# blinds_new.net
KiCad netlist of a schematic drawn in EAGLE
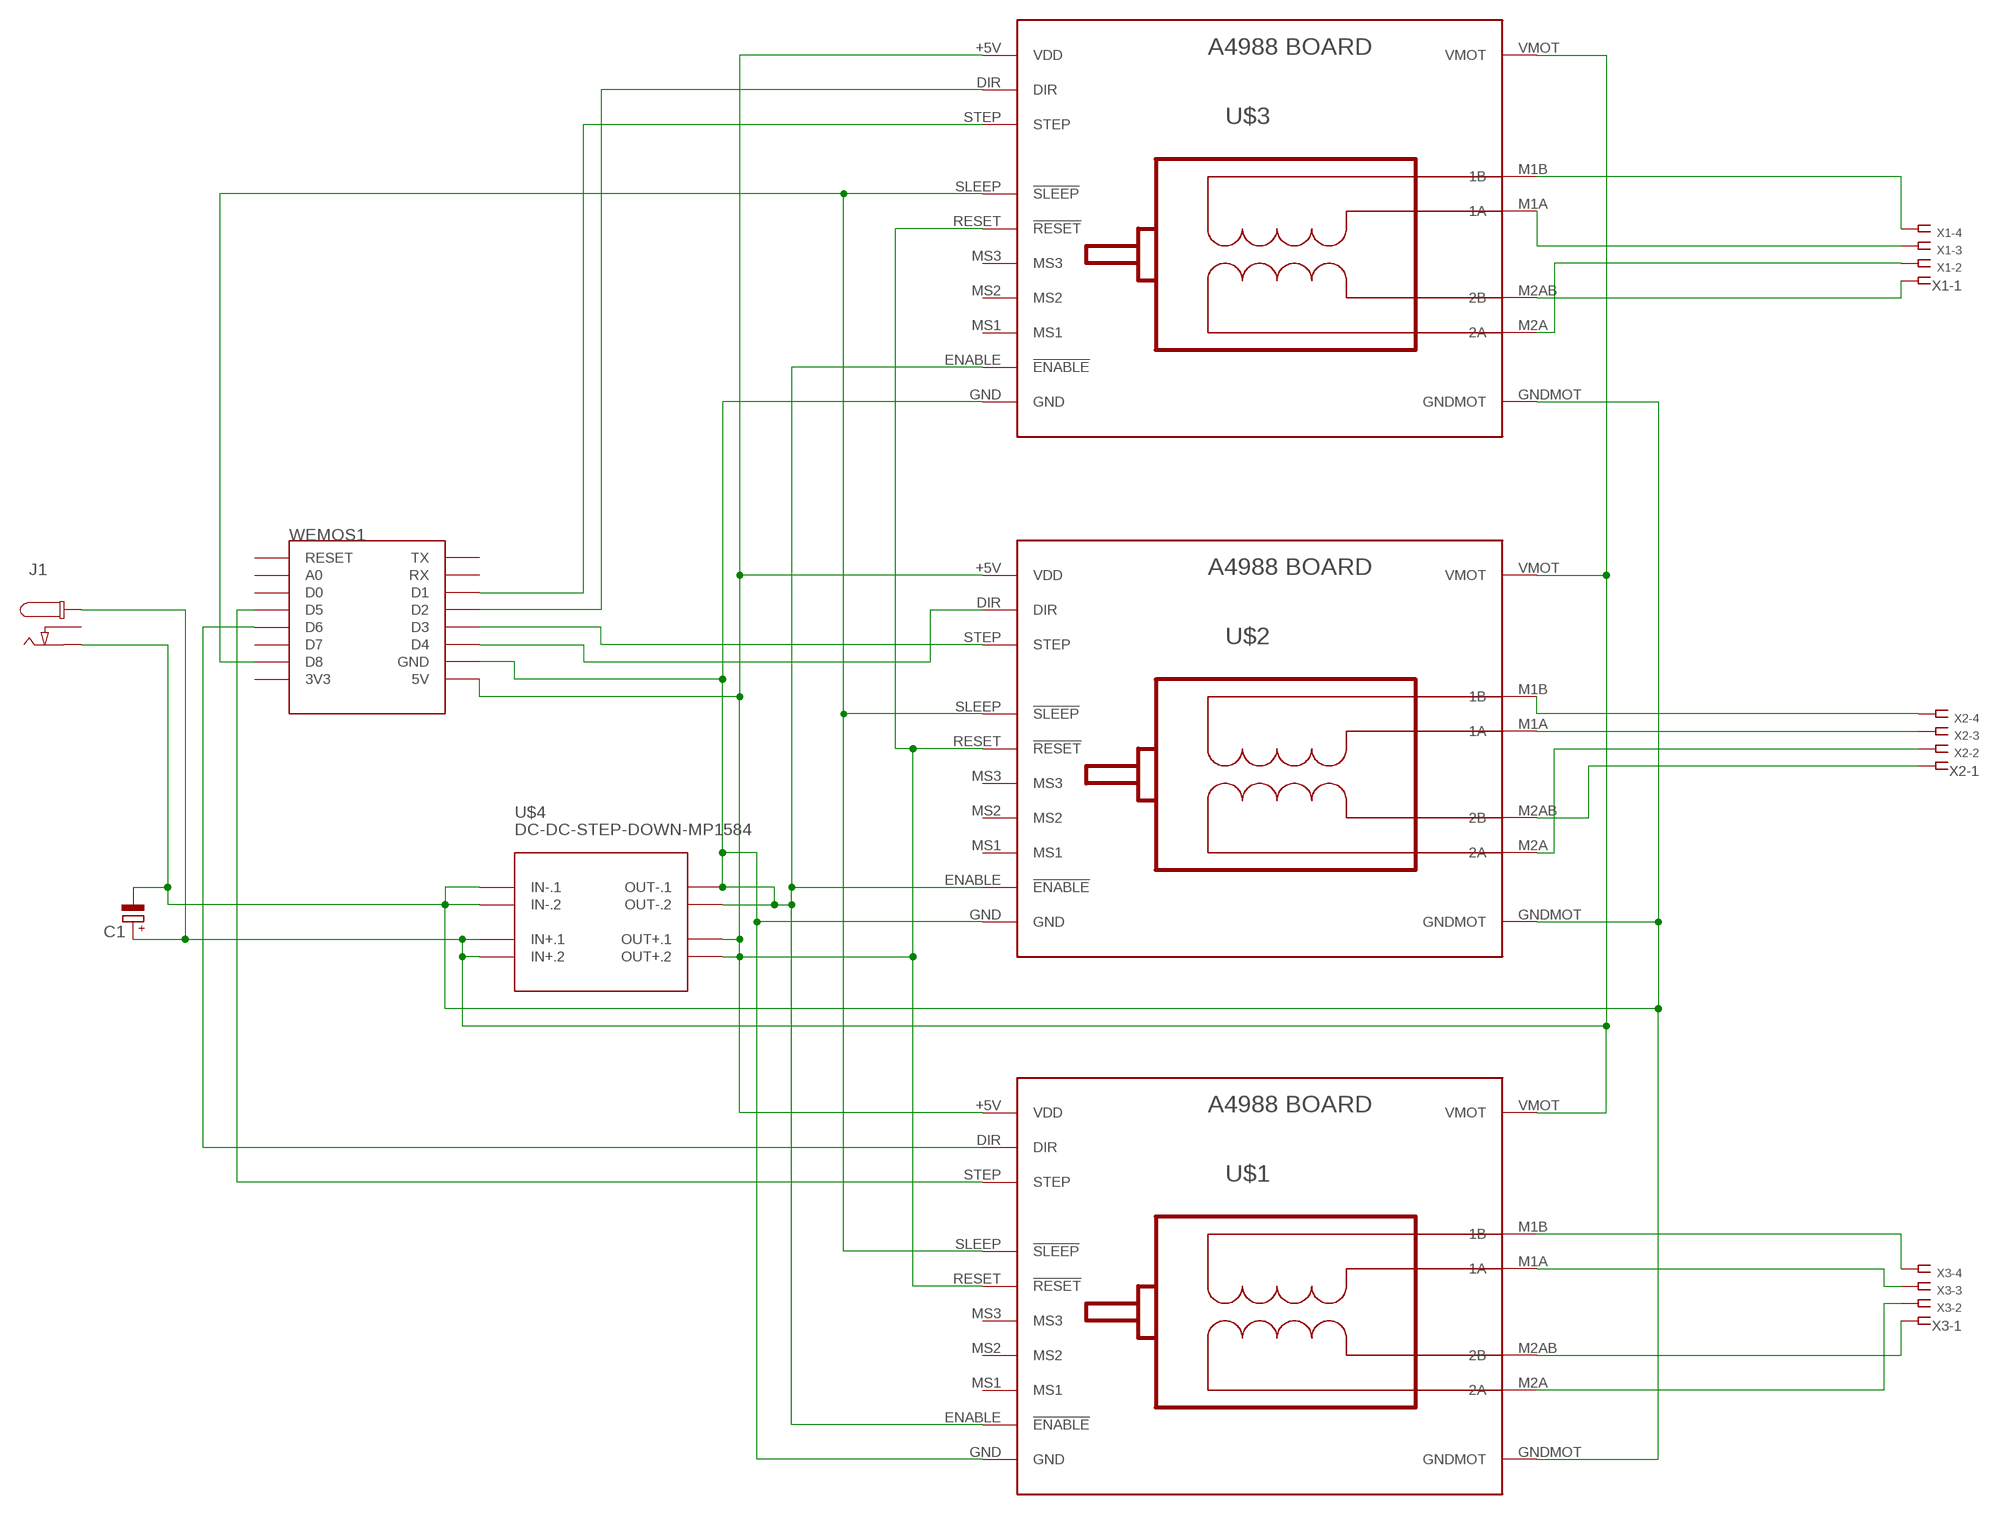
[diagram p0: schematic, sheet 1]

(export (version "E")
  (design (tool "Eeschema 10.0.6"))
  (components
    (comp (ref "C1")
      (value "CPOL-EUE1.8-4")
      (footprint "eagle-import:E1,8-4")
      (libsource (lib "eagle-import") (part "CPOL-EUE1.8-4"))
    )
    (comp (ref "J1")
      (value "CON_DC_M-DC_SMD")
      (footprint "eagle-import:DC_BARREL_JACK_SMD_2MM")
      (libsource (lib "eagle-import") (part "CON_DC_M-DC_SMD"))
    )
    (comp (ref "U$1")
      (value "BOARD_A4988")
      (footprint "eagle-import:BOARD_A4988")
      (libsource (lib "eagle-import") (part "BOARD_A4988"))
    )
    (comp (ref "U$2")
      (value "BOARD_A4988")
      (footprint "eagle-import:BOARD_A4988")
      (libsource (lib "eagle-import") (part "BOARD_A4988"))
    )
    (comp (ref "U$3")
      (value "BOARD_A4988")
      (footprint "eagle-import:BOARD_A4988")
      (libsource (lib "eagle-import") (part "BOARD_A4988"))
    )
    (comp (ref "U$4")
      (value "DC-DC-STEP-DOWN-MP1584")
      (footprint "eagle-import:DC-DC-STEP-DOWN-MP1584")
      (libsource (lib "eagle-import") (part "DC-DC-STEP-DOWN-MP1584"))
    )
    (comp (ref "WEMOS1")
      (value "WEMOS-D1-MINI")
      (footprint "eagle-import:WEMOS-D1-MINI")
      (libsource (lib "eagle-import") (part "WEMOS-D1-MINI"))
    )
    (comp (ref "X1")
      (value "SSW-104-02-S-S")
      (footprint "eagle-import:SSW-104-02-S-S")
      (libsource (lib "eagle-import") (part "SSW-104-02-S-S"))
    )
    (comp (ref "X2")
      (value "SSW-104-02-S-S")
      (footprint "eagle-import:SSW-104-02-S-S")
      (libsource (lib "eagle-import") (part "SSW-104-02-S-S"))
    )
    (comp (ref "X3")
      (value "SSW-104-02-S-S")
      (footprint "eagle-import:SSW-104-02-S-S")
      (libsource (lib "eagle-import") (part "SSW-104-02-S-S"))
    )
  )
  (nets
    (net (code "1") (name "Net-(C1-Pad-)") (class "Default")
      (node (ref "C1") (pin "-") (pinfunction "-_-") (pintype "passive"))
      (node (ref "J1") (pin "P2") (pinfunction "P2_P2") (pintype "passive"))
      (node (ref "U$1") (pin "GNDMOT") (pinfunction "GNDMOT_GNDMOT") (pintype "power_in"))
      (node (ref "U$2") (pin "GNDMOT") (pinfunction "GNDMOT_GNDMOT") (pintype "power_in"))
      (node (ref "U$3") (pin "GNDMOT") (pinfunction "GNDMOT_GNDMOT") (pintype "power_in"))
      (node (ref "U$4") (pin "IN-.1") (pinfunction "IN-.1_IN-.1") (pintype "bidirectional"))
      (node (ref "U$4") (pin "IN-.2") (pinfunction "IN-.2_IN-.2") (pintype "bidirectional"))
    )
    (net (code "2") (name "Net-(J1-P1)") (class "Default")
      (node (ref "C1") (pin "+") (pinfunction "+_+") (pintype "passive"))
      (node (ref "J1") (pin "P1@2") (pinfunction "P1_P1@2") (pintype "passive"))
      (node (ref "U$1") (pin "VMOT") (pinfunction "VMOT_VMOT") (pintype "power_in"))
      (node (ref "U$2") (pin "VMOT") (pinfunction "VMOT_VMOT") (pintype "power_in"))
      (node (ref "U$3") (pin "VMOT") (pinfunction "VMOT_VMOT") (pintype "power_in"))
      (node (ref "U$4") (pin "IN+.1") (pinfunction "IN+.1_IN+.1") (pintype "bidirectional"))
      (node (ref "U$4") (pin "IN+.2") (pinfunction "IN+.2_IN+.2") (pintype "bidirectional"))
    )
    (net (code "3") (name "Net-(U$1-1A)") (class "Default")
      (node (ref "U$1") (pin "M1A") (pinfunction "1A_M1A") (pintype "output"))
      (node (ref "X3") (pin "3") (pinfunction "1_3") (pintype "passive"))
    )
    (net (code "4") (name "Net-(U$1-1B)") (class "Default")
      (node (ref "U$1") (pin "M1B") (pinfunction "1B_M1B") (pintype "output"))
      (node (ref "X3") (pin "4") (pinfunction "1_4") (pintype "passive"))
    )
    (net (code "5") (name "Net-(U$1-2A)") (class "Default")
      (node (ref "U$1") (pin "M2A") (pinfunction "2A_M2A") (pintype "output"))
      (node (ref "X3") (pin "2") (pinfunction "1_2") (pintype "passive"))
    )
    (net (code "6") (name "Net-(U$1-2B)") (class "Default")
      (node (ref "U$1") (pin "M2AB") (pinfunction "2B_M2AB") (pintype "output"))
      (node (ref "X3") (pin "1") (pinfunction "1_1") (pintype "passive"))
    )
    (net (code "7") (name "Net-(U$1-PadDIR)") (class "Default")
      (node (ref "U$1") (pin "DIR") (pinfunction "DIR_DIR") (pintype "input"))
      (node (ref "WEMOS1") (pin "D6") (pinfunction "D6_D6") (pintype "bidirectional"))
    )
    (net (code "8") (name "Net-(U$1-PadSTEP)") (class "Default")
      (node (ref "U$1") (pin "STEP") (pinfunction "STEP_STEP") (pintype "input"))
      (node (ref "WEMOS1") (pin "D5") (pinfunction "D5_D5") (pintype "bidirectional"))
    )
    (net (code "9") (name "Net-(U$1-VDD)") (class "Default")
      (node (ref "U$1") (pin "+5V") (pinfunction "VDD_+5V") (pintype "power_in"))
      (node (ref "U$1") (pin "RESET") (pinfunction "~{RESET}_RESET") (pintype "input"))
      (node (ref "U$2") (pin "+5V") (pinfunction "VDD_+5V") (pintype "power_in"))
      (node (ref "U$2") (pin "RESET") (pinfunction "~{RESET}_RESET") (pintype "input"))
      (node (ref "U$3") (pin "+5V") (pinfunction "VDD_+5V") (pintype "power_in"))
      (node (ref "U$3") (pin "RESET") (pinfunction "~{RESET}_RESET") (pintype "input"))
      (node (ref "U$4") (pin "OUT+.1") (pinfunction "OUT+.1_OUT+.1") (pintype "bidirectional"))
      (node (ref "U$4") (pin "OUT+.2") (pinfunction "OUT+.2_OUT+.2") (pintype "bidirectional"))
      (node (ref "WEMOS1") (pin "5V") (pinfunction "5V_5V") (pintype "bidirectional"))
    )
    (net (code "10") (name "Net-(U$1-~{ENABLE})") (class "Default")
      (node (ref "U$1") (pin "ENABLE") (pinfunction "~{ENABLE}_ENABLE") (pintype "input"))
      (node (ref "U$1") (pin "GND") (pinfunction "GND_GND") (pintype "power_in"))
      (node (ref "U$2") (pin "ENABLE") (pinfunction "~{ENABLE}_ENABLE") (pintype "input"))
      (node (ref "U$2") (pin "GND") (pinfunction "GND_GND") (pintype "power_in"))
      (node (ref "U$3") (pin "ENABLE") (pinfunction "~{ENABLE}_ENABLE") (pintype "input"))
      (node (ref "U$3") (pin "GND") (pinfunction "GND_GND") (pintype "power_in"))
      (node (ref "U$4") (pin "OUT-.1") (pinfunction "OUT-.1_OUT-.1") (pintype "bidirectional"))
      (node (ref "U$4") (pin "OUT-.2") (pinfunction "OUT-.2_OUT-.2") (pintype "bidirectional"))
      (node (ref "WEMOS1") (pin "GND") (pinfunction "GND_GND") (pintype "bidirectional"))
    )
    (net (code "11") (name "Net-(U$1-~{SLEEP})") (class "Default")
      (node (ref "U$1") (pin "SLEEP") (pinfunction "~{SLEEP}_SLEEP") (pintype "input"))
      (node (ref "U$2") (pin "SLEEP") (pinfunction "~{SLEEP}_SLEEP") (pintype "input"))
      (node (ref "U$3") (pin "SLEEP") (pinfunction "~{SLEEP}_SLEEP") (pintype "input"))
      (node (ref "WEMOS1") (pin "D8") (pinfunction "D8_D8") (pintype "bidirectional"))
    )
    (net (code "12") (name "Net-(U$2-1A)") (class "Default")
      (node (ref "U$2") (pin "M1A") (pinfunction "1A_M1A") (pintype "output"))
      (node (ref "X2") (pin "3") (pinfunction "1_3") (pintype "passive"))
    )
    (net (code "13") (name "Net-(U$2-1B)") (class "Default")
      (node (ref "U$2") (pin "M1B") (pinfunction "1B_M1B") (pintype "output"))
      (node (ref "X2") (pin "4") (pinfunction "1_4") (pintype "passive"))
    )
    (net (code "14") (name "Net-(U$2-2A)") (class "Default")
      (node (ref "U$2") (pin "M2A") (pinfunction "2A_M2A") (pintype "output"))
      (node (ref "X2") (pin "2") (pinfunction "1_2") (pintype "passive"))
    )
    (net (code "15") (name "Net-(U$2-2B)") (class "Default")
      (node (ref "U$2") (pin "M2AB") (pinfunction "2B_M2AB") (pintype "output"))
      (node (ref "X2") (pin "1") (pinfunction "1_1") (pintype "passive"))
    )
    (net (code "16") (name "Net-(U$2-PadDIR)") (class "Default")
      (node (ref "U$2") (pin "DIR") (pinfunction "DIR_DIR") (pintype "input"))
      (node (ref "WEMOS1") (pin "D4") (pinfunction "D4_D4") (pintype "bidirectional"))
    )
    (net (code "17") (name "Net-(U$2-PadSTEP)") (class "Default")
      (node (ref "U$2") (pin "STEP") (pinfunction "STEP_STEP") (pintype "input"))
      (node (ref "WEMOS1") (pin "D3") (pinfunction "D3_D3") (pintype "bidirectional"))
    )
    (net (code "18") (name "Net-(U$3-1A)") (class "Default")
      (node (ref "U$3") (pin "M1A") (pinfunction "1A_M1A") (pintype "output"))
      (node (ref "X1") (pin "3") (pinfunction "1_3") (pintype "passive"))
    )
    (net (code "19") (name "Net-(U$3-1B)") (class "Default")
      (node (ref "U$3") (pin "M1B") (pinfunction "1B_M1B") (pintype "output"))
      (node (ref "X1") (pin "4") (pinfunction "1_4") (pintype "passive"))
    )
    (net (code "20") (name "Net-(U$3-2A)") (class "Default")
      (node (ref "U$3") (pin "M2A") (pinfunction "2A_M2A") (pintype "output"))
      (node (ref "X1") (pin "2") (pinfunction "1_2") (pintype "passive"))
    )
    (net (code "21") (name "Net-(U$3-2B)") (class "Default")
      (node (ref "U$3") (pin "M2AB") (pinfunction "2B_M2AB") (pintype "output"))
      (node (ref "X1") (pin "1") (pinfunction "1_1") (pintype "passive"))
    )
    (net (code "22") (name "Net-(U$3-PadDIR)") (class "Default")
      (node (ref "U$3") (pin "DIR") (pinfunction "DIR_DIR") (pintype "input"))
      (node (ref "WEMOS1") (pin "D2") (pinfunction "D2_D2") (pintype "bidirectional"))
    )
    (net (code "23") (name "Net-(U$3-PadSTEP)") (class "Default")
      (node (ref "U$3") (pin "STEP") (pinfunction "STEP_STEP") (pintype "input"))
      (node (ref "WEMOS1") (pin "D1") (pinfunction "D1_D1") (pintype "bidirectional"))
    )
    (net (code "24") (name "unconnected-(J1-PadP3)") (class "Default")
      (node (ref "J1") (pin "P3") (pinfunction "P3_P3") (pintype "passive"))
    )
    (net (code "25") (name "unconnected-(U$1-PadMS1)") (class "Default")
      (node (ref "U$1") (pin "MS1") (pinfunction "MS1_MS1") (pintype "input"))
    )
    (net (code "26") (name "unconnected-(U$1-PadMS2)") (class "Default")
      (node (ref "U$1") (pin "MS2") (pinfunction "MS2_MS2") (pintype "input"))
    )
    (net (code "27") (name "unconnected-(U$1-PadMS3)") (class "Default")
      (node (ref "U$1") (pin "MS3") (pinfunction "MS3_MS3") (pintype "input"))
    )
    (net (code "28") (name "unconnected-(U$2-PadMS1)") (class "Default")
      (node (ref "U$2") (pin "MS1") (pinfunction "MS1_MS1") (pintype "input"))
    )
    (net (code "29") (name "unconnected-(U$2-PadMS2)") (class "Default")
      (node (ref "U$2") (pin "MS2") (pinfunction "MS2_MS2") (pintype "input"))
    )
    (net (code "30") (name "unconnected-(U$2-PadMS3)") (class "Default")
      (node (ref "U$2") (pin "MS3") (pinfunction "MS3_MS3") (pintype "input"))
    )
    (net (code "31") (name "unconnected-(U$3-PadMS1)") (class "Default")
      (node (ref "U$3") (pin "MS1") (pinfunction "MS1_MS1") (pintype "input"))
    )
    (net (code "32") (name "unconnected-(U$3-PadMS2)") (class "Default")
      (node (ref "U$3") (pin "MS2") (pinfunction "MS2_MS2") (pintype "input"))
    )
    (net (code "33") (name "unconnected-(U$3-PadMS3)") (class "Default")
      (node (ref "U$3") (pin "MS3") (pinfunction "MS3_MS3") (pintype "input"))
    )
    (net (code "34") (name "unconnected-(WEMOS1-Pad3V3)") (class "Default")
      (node (ref "WEMOS1") (pin "3V3") (pinfunction "3V3_3V3") (pintype "bidirectional"))
    )
    (net (code "35") (name "unconnected-(WEMOS1-PadA0)") (class "Default")
      (node (ref "WEMOS1") (pin "A0") (pinfunction "A0_A0") (pintype "bidirectional"))
    )
    (net (code "36") (name "unconnected-(WEMOS1-PadD0)") (class "Default")
      (node (ref "WEMOS1") (pin "D0") (pinfunction "D0_D0") (pintype "bidirectional"))
    )
    (net (code "37") (name "unconnected-(WEMOS1-PadD7)") (class "Default")
      (node (ref "WEMOS1") (pin "D7") (pinfunction "D7_D7") (pintype "bidirectional"))
    )
    (net (code "38") (name "unconnected-(WEMOS1-PadRESET)") (class "Default")
      (node (ref "WEMOS1") (pin "RESET") (pinfunction "RESET_RESET") (pintype "bidirectional"))
    )
    (net (code "39") (name "unconnected-(WEMOS1-PadRX)") (class "Default")
      (node (ref "WEMOS1") (pin "RX") (pinfunction "RX_RX") (pintype "bidirectional"))
    )
    (net (code "40") (name "unconnected-(WEMOS1-PadTX)") (class "Default")
      (node (ref "WEMOS1") (pin "TX") (pinfunction "TX_TX") (pintype "bidirectional"))
    )
  )
)
